# MICROCONTROLLER.net
KiCad netlist of a schematic drawn in Altium Designer
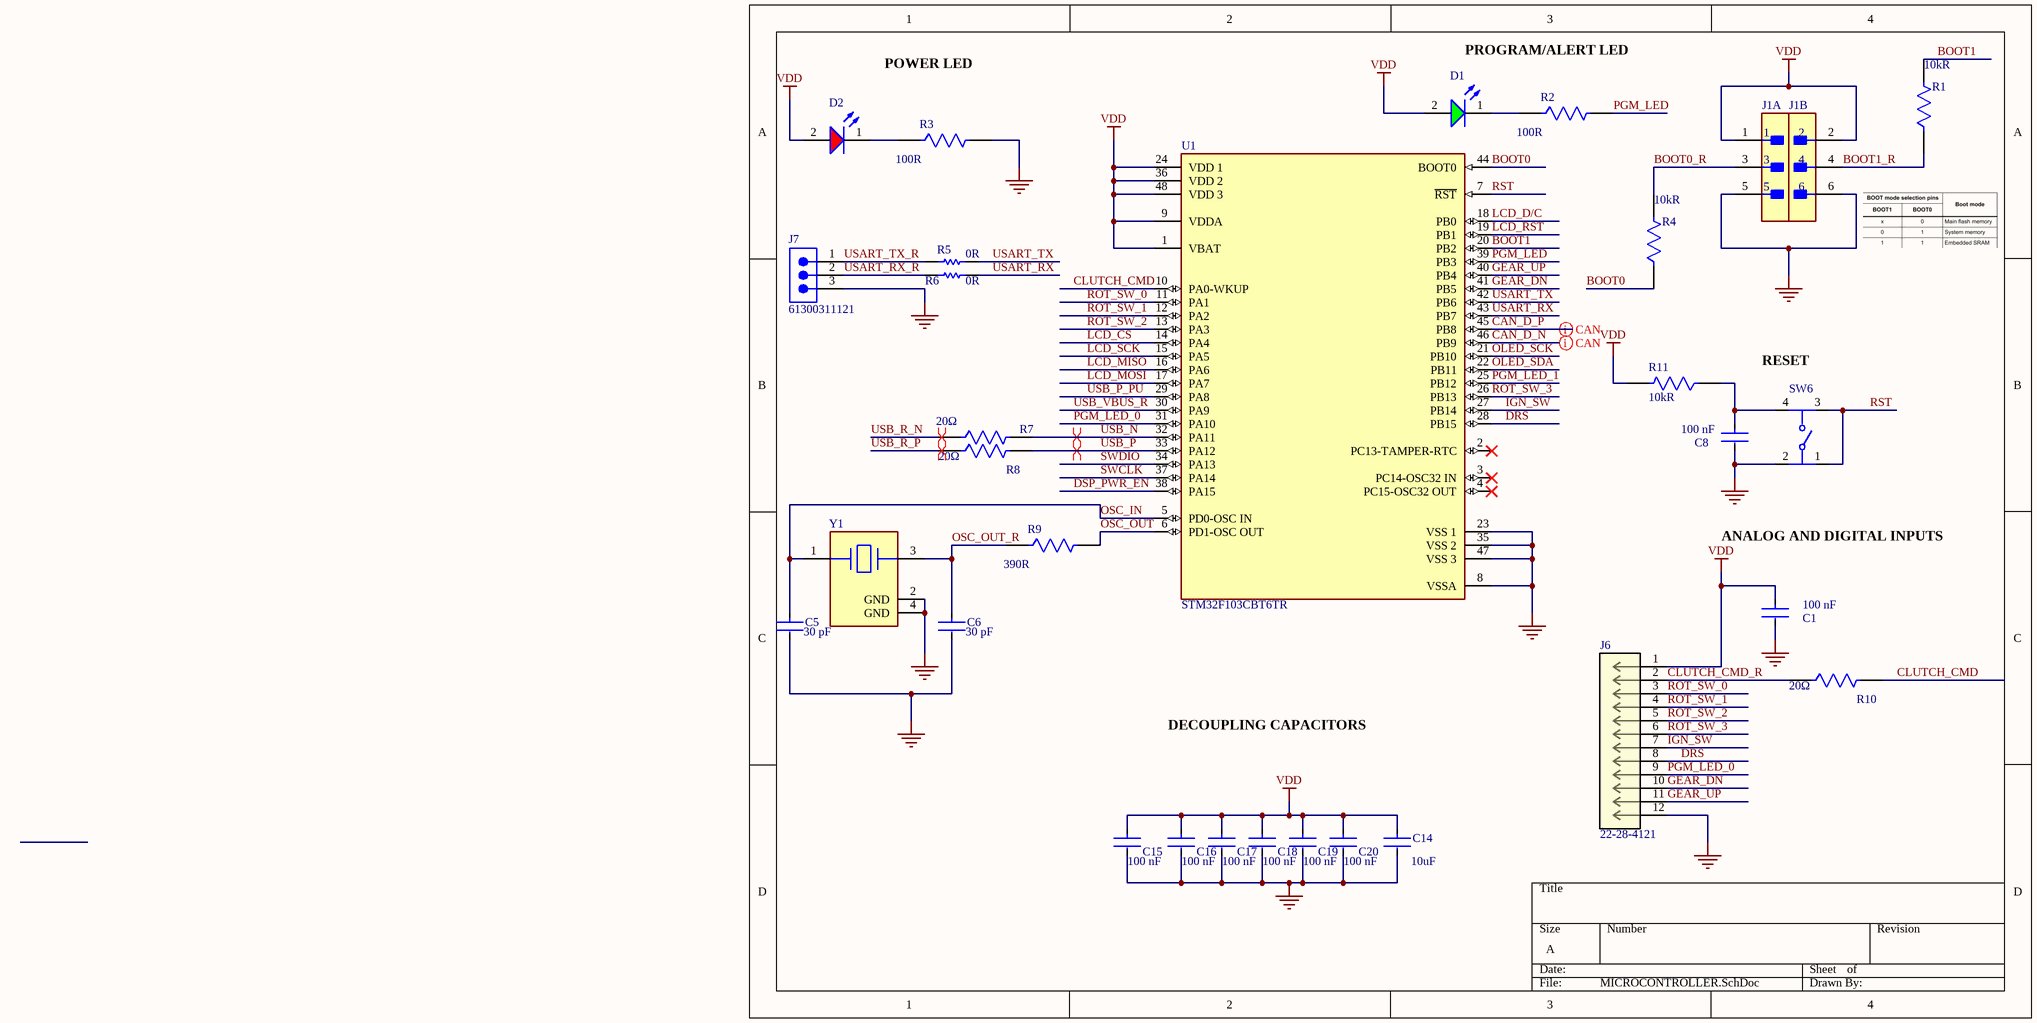
[diagram p0: MICROCONTROLLER.SchDoc]

(export (version "E")
  (design (tool "Eeschema 10.0.6"))
  (components
    (comp (ref "C1")
      (value "CC0402KRX7R7BB104")
      (footprint "FP-CC0402-MFG")
      (description "CAP CER 0.1UF 16V X7R 0402")
      (fields
        (field (name "CAPACITANCE") "100 nF")
        (field (name "MANUFACTURER") "YAGEO")
        (field (name "TOLERANCE") "0.1")
      )
      (libsource (lib "Altium Content Vault") (part "11868f565c42a9108669ba33697ecf6"))
    )
    (comp (ref "C5")
      (value "C0603C300F3HACAUTO")
      (footprint "FP-C0603C-CF-MFG")
      (description "C0603 30 pF X8R 30ppm/°C 1.00% 25 V")
      (fields
        (field (name "MANUFACTURER") "KEMET")
        (field (name "CAPACITANCE") "30 pF")
        (field (name "OCTOPART") "https://octopart.com/c0603c300f3hacauto-kemet-88087312")
      )
      (libsource (lib "Altium Content Vault") (part "b4654b650e69147ec39a6b967a45e02"))
    )
    (comp (ref "C6")
      (value "C0603C300F3HACAUTO")
      (footprint "FP-C0603C-CF-MFG")
      (description "C0603 30 pF X8R 30ppm/°C 1.00% 25 V")
      (fields
        (field (name "MANUFACTURER") "KEMET")
        (field (name "CAPACITANCE") "30 pF")
        (field (name "OCTOPART") "https://octopart.com/c0603c300f3hacauto-kemet-88087312")
      )
      (libsource (lib "Altium Content Vault") (part "b4654b650e69147ec39a6b967a45e02"))
    )
    (comp (ref "C8")
      (value "CC0402KRX7R7BB104")
      (footprint "FP-CC0402-MFG")
      (description "CAP CER 0.1UF 16V X7R 0402")
      (fields
        (field (name "CAPACITANCE") "100 nF")
        (field (name "MANUFACTURER") "YAGEO")
        (field (name "TOLERANCE") "0.1")
      )
      (libsource (lib "Altium Content Vault") (part "11868f565c42a9108669ba33697ecf6"))
    )
    (comp (ref "C14")
      (value "EMK212BB7106KG-T")
      (footprint "FP-0805-L_2_0_0_2-W_1_25-MFG")
      (description "CAP CER 10UF 16V X7R 0805")
      (fields (field (name "TOLERANCE") "10%") (field (name "CAPACITANCE") "10uF"))
      (libsource (lib "Altium Content Vault") (part "b4654b650e69147ec39a6b967a45e02"))
    )
    (comp (ref "C15")
      (value "CC0402KRX7R7BB104")
      (footprint "FP-CC0402-MFG")
      (description "CAP CER 0.1UF 16V X7R 0402")
      (fields
        (field (name "CAPACITANCE") "100 nF")
        (field (name "MANUFACTURER") "YAGEO")
        (field (name "TOLERANCE") "0.1")
      )
      (libsource (lib "Altium Content Vault") (part "11868f565c42a9108669ba33697ecf6"))
    )
    (comp (ref "C16")
      (value "CC0402KRX7R7BB104")
      (footprint "FP-CC0402-MFG")
      (description "CAP CER 0.1UF 16V X7R 0402")
      (fields
        (field (name "CAPACITANCE") "100 nF")
        (field (name "MANUFACTURER") "YAGEO")
        (field (name "TOLERANCE") "0.1")
      )
      (libsource (lib "Altium Content Vault") (part "11868f565c42a9108669ba33697ecf6"))
    )
    (comp (ref "C17")
      (value "CC0402KRX7R7BB104")
      (footprint "FP-CC0402-MFG")
      (description "CAP CER 0.1UF 16V X7R 0402")
      (fields
        (field (name "CAPACITANCE") "100 nF")
        (field (name "MANUFACTURER") "YAGEO")
        (field (name "TOLERANCE") "0.1")
      )
      (libsource (lib "Altium Content Vault") (part "11868f565c42a9108669ba33697ecf6"))
    )
    (comp (ref "C18")
      (value "CC0402KRX7R7BB104")
      (footprint "FP-CC0402-MFG")
      (description "CAP CER 0.1UF 16V X7R 0402")
      (fields
        (field (name "CAPACITANCE") "100 nF")
        (field (name "MANUFACTURER") "YAGEO")
        (field (name "TOLERANCE") "0.1")
      )
      (libsource (lib "Altium Content Vault") (part "11868f565c42a9108669ba33697ecf6"))
    )
    (comp (ref "C19")
      (value "CC0402KRX7R7BB104")
      (footprint "FP-CC0402-MFG")
      (description "CAP CER 0.1UF 16V X7R 0402")
      (fields
        (field (name "CAPACITANCE") "100 nF")
        (field (name "MANUFACTURER") "YAGEO")
        (field (name "TOLERANCE") "0.1")
      )
      (libsource (lib "Altium Content Vault") (part "11868f565c42a9108669ba33697ecf6"))
    )
    (comp (ref "C20")
      (value "CC0402KRX7R7BB104")
      (footprint "FP-CC0402-MFG")
      (description "CAP CER 0.1UF 16V X7R 0402")
      (fields
        (field (name "CAPACITANCE") "100 nF")
        (field (name "MANUFACTURER") "YAGEO")
        (field (name "TOLERANCE") "0.1")
      )
      (libsource (lib "Altium Content Vault") (part "11868f565c42a9108669ba33697ecf6"))
    )
    (comp (ref "D1")
      (value "150060VS75000")
      (footprint "WL-SMCW_0603_150060xx75000")
      (description "WURTH ELEKTRONIK - 150060VS75000 - LED, Green, SMD, 0603, 30 mA, 2 V, 570 nm")
      (libsource (lib "Altium Content Vault") (part "LED_Green_2A-1K"))
    )
    (comp (ref "D2")
      (value "150080RS75000")
      (footprint "WL-SMCW_0805_150080xx75000")
      (description "LED Uni-Color Red 630nm 2-Pin Chip 0805(2012Metric) T/R")
      (libsource (lib "Altium Content Vault") (part "LED_Red_2A-1K"))
    )
    (comp (ref "J1")
      (value "FTSH-103-01-F-DV-TR")
      (footprint "FP-FTSH-103-01-F-DV-TR-MFG")
      (description "CONN HEADER SMD 6POS 1.27MM")
      (libsource (lib "") (part "2654a11fb13586ecb194516b1c997bc_1"))
    )
    (comp (ref "J6")
      (value "22-28-4121")
      (footprint "12 POS_2.54MM_MOLEX")
      (description "KK 254 Breakaway Header, Vertical, 12 Circuits, Tin (Sn) Plating, Mating Pin Length 8.13mm")
      (fields (field (name "MANUFACTURER") "Molex"))
      (libsource (lib "F1_MODULE") (part "22-28-4121"))
    )
    (comp (ref "J7")
      (value "61300311121")
      (footprint "61300311121")
      (description "CONN HEADER VERT 3POS 2.54MM")
      (libsource (lib "Altium Content Vault") (part "Header_Male_1R_03P"))
    )
    (comp (ref "R1")
      (value "RC0402JR-0710KL")
      (footprint "FP-RC0402-0_4-MFG")
      (description "RES 10K OHM 5% 1/16W 0402")
      (fields (field (name "RESISTANCE") "10kR") (field (name "TOLERANCE") "5%"))
      (libsource (lib "Altium Content Vault") (part "1029c3af85768c4190bb7ad29bc67b5"))
    )
    (comp (ref "R2")
      (value "MCS0402MC1000FE000")
      (footprint "FP-MCS0402-MFG")
      (description "RES SMD 1.2K OHM 1% 1/10W 0402")
      (fields (field (name "RESISTANCE") "100R") (field (name "TOLERANCE") "1%"))
      (libsource (lib "Altium Content Vault") (part "1029c3af85768c4190bb7ad29bc67b5"))
    )
    (comp (ref "R3")
      (value "MCS0402MC1000FE000")
      (footprint "FP-MCS0402-MFG")
      (description "RES SMD 1.2K OHM 1% 1/10W 0402")
      (fields (field (name "RESISTANCE") "100R") (field (name "TOLERANCE") "1%"))
      (libsource (lib "Altium Content Vault") (part "1029c3af85768c4190bb7ad29bc67b5"))
    )
    (comp (ref "R4")
      (value "RC0402JR-0710KL")
      (footprint "FP-RC0402-0_4-MFG")
      (description "RES 10K OHM 5% 1/16W 0402")
      (fields (field (name "RESISTANCE") "10kR") (field (name "TOLERANCE") "5%"))
      (libsource (lib "Altium Content Vault") (part "1029c3af85768c4190bb7ad29bc67b5"))
    )
    (comp (ref "R5")
      (value "ERJ2GE0R00X")
      (footprint "RESC1005X40X25LL05T05")
      (description "Chip Resistor, 0 Ohm, 0.1 W, -55 to 155 degC, 0402 (1005 Metric), RoHS, Tape and Reel")
      (fields
        (field (name "MANUFACTURER") "Panasonic")
        (field (name "RESISTANCE") "0R")
        (field (name "TOLERANCE") "5%")
      )
      (libsource (lib "Altium Content Vault") (part "RES-2"))
    )
    (comp (ref "R6")
      (value "ERJ2GE0R00X")
      (footprint "RESC1005X40X25LL05T05")
      (description "Chip Resistor, 0 Ohm, 0.1 W, -55 to 155 degC, 0402 (1005 Metric), RoHS, Tape and Reel")
      (fields
        (field (name "MANUFACTURER") "Panasonic")
        (field (name "RESISTANCE") "0R")
        (field (name "TOLERANCE") "5%")
      )
      (libsource (lib "Altium Content Vault") (part "RES-2"))
    )
    (comp (ref "R7")
      (value "RT0402FRE0720RL")
      (footprint "FP-RT0402-MFG")
      (description "RES SMD 20 OHM 1% 1/16W 0402")
      (fields
        (field (name "RESISTANCE") "20Ω")
        (field (name "MANUFACTURER") "Yageo")
        (field (name "OCTOPART") "https://octopart.com/rt0402fre0720rl-yageo-1278881")
      )
      (libsource (lib "Altium Content Vault") (part "1029c3af85768c4190bb7ad29bc67b5"))
    )
    (comp (ref "R8")
      (value "RT0402FRE0720RL")
      (footprint "FP-RT0402-MFG")
      (description "RES SMD 20 OHM 1% 1/16W 0402")
      (fields
        (field (name "RESISTANCE") "20Ω")
        (field (name "MANUFACTURER") "Yageo")
        (field (name "OCTOPART") "https://octopart.com/rt0402fre0720rl-yageo-1278881")
      )
      (libsource (lib "Altium Content Vault") (part "1029c3af85768c4190bb7ad29bc67b5"))
    )
    (comp (ref "R9")
      (value "CRCW0402390RFKED")
      (footprint "FP-CRCW0402-e3-MFG")
      (description "RES Thick Film, 390Ω, 1%, 0.063W, 100ppm/°C, 0402")
      (fields (field (name "RESISTANCE") "390R") (field (name "TOLERANCE") "1%"))
      (libsource (lib "Altium Content Vault") (part "1029c3af85768c4190bb7ad29bc67b5"))
    )
    (comp (ref "R10")
      (value "RT0402FRE0720RL")
      (footprint "FP-RT0402-MFG")
      (description "RES SMD 20 OHM 1% 1/16W 0402")
      (fields
        (field (name "RESISTANCE") "20Ω")
        (field (name "MANUFACTURER") "Yageo")
        (field (name "OCTOPART") "https://octopart.com/rt0402fre0720rl-yageo-1278881")
      )
      (libsource (lib "Altium Content Vault") (part "1029c3af85768c4190bb7ad29bc67b5"))
    )
    (comp (ref "R11")
      (value "RC0402JR-0710KL")
      (footprint "FP-RC0402-0_4-MFG")
      (description "RES 10K OHM 5% 1/16W 0402")
      (fields (field (name "RESISTANCE") "10kR") (field (name "TOLERANCE") "5%"))
      (libsource (lib "Altium Content Vault") (part "1029c3af85768c4190bb7ad29bc67b5"))
    )
    (comp (ref "SW6")
      (value "1977223-4")
      (footprint "FP-1977223-4-MFG")
      (description "SWITCH TACTILE SPST-NO 0.05A 12V")
      (libsource (lib "Altium Content Vault") (part "b8895f3f4cefb76e1819d2863dba89b"))
    )
    (comp (ref "U1")
      (value "STM32F103CBT6TR")
      (footprint "FP-LQFP48-5B-MFG")
      (description "ARM® Cortex®-M3 STM32F1 Microcontroller IC 32-Bit 72MHz 128KB (128K x 8) FLASH")
      (libsource (lib "Altium Content Vault") (part "2bc3fe5586cf3d28b17275e4580a88a"))
    )
    (comp (ref "Y1")
      (value "ABM3BAIG-8.000MHZ-1Z-T")
      (footprint "FP-ABM3BAIG-MFG")
      (description "CRYSTAL 8.0000MHZ 18PF SMD")
      (libsource (lib "Altium Content Vault") (part "3dd7ae69e6a56028198fd7abc02d048"))
    )
  )
  (nets
    (net (code "1") (name "/BOOT0") (class "Default")
      (node (ref "R4") (pin "1") (pinfunction "1_1") (pintype "passive"))
      (node (ref "U1") (pin "44") (pinfunction "BOOT0_44") (pintype "input"))
    )
    (net (code "2") (name "/BOOT0_R") (class "Default")
      (node (ref "J1") (pin "3") (pinfunction "3_3") (pintype "passive"))
      (node (ref "R4") (pin "2") (pinfunction "2_2") (pintype "passive"))
    )
    (net (code "3") (name "/BOOT1") (class "Default")
      (node (ref "R1") (pin "2") (pinfunction "2_2") (pintype "passive"))
      (node (ref "U1") (pin "20") (pinfunction "PB2_20") (pintype "bidirectional"))
    )
    (net (code "4") (name "/BOOT1_R") (class "Default")
      (node (ref "J1") (pin "4") (pinfunction "4_4") (pintype "passive"))
      (node (ref "R1") (pin "1") (pinfunction "1_1") (pintype "passive"))
    )
    (net (code "5") (name "/CAN_D_N") (class "Default")
      (node (ref "U1") (pin "46") (pinfunction "PB9_46") (pintype "bidirectional"))
    )
    (net (code "6") (name "/CAN_D_P") (class "Default")
      (node (ref "U1") (pin "45") (pinfunction "PB8_45") (pintype "bidirectional"))
    )
    (net (code "7") (name "/CLUTCH_CMD") (class "Default")
      (node (ref "R10") (pin "2") (pinfunction "2_2") (pintype "passive"))
      (node (ref "U1") (pin "10") (pinfunction "PA0-WKUP_10") (pintype "bidirectional"))
    )
    (net (code "8") (name "/CLUTCH_CMD_R") (class "Default")
      (node (ref "J6") (pin "2") (pinfunction "2_2") (pintype "passive"))
      (node (ref "R10") (pin "1") (pinfunction "1_1") (pintype "passive"))
    )
    (net (code "9") (name "/DRS") (class "Default")
      (node (ref "J6") (pin "8") (pinfunction "8_8") (pintype "passive"))
      (node (ref "U1") (pin "28") (pinfunction "PB15_28") (pintype "bidirectional"))
    )
    (net (code "10") (name "/DSP_PWR_EN") (class "Default")
      (node (ref "U1") (pin "38") (pinfunction "PA15_38") (pintype "bidirectional"))
    )
    (net (code "11") (name "/GEAR_DN") (class "Default")
      (node (ref "J6") (pin "10") (pinfunction "10_10") (pintype "passive"))
      (node (ref "U1") (pin "41") (pinfunction "PB5_41") (pintype "bidirectional"))
    )
    (net (code "12") (name "/GEAR_UP") (class "Default")
      (node (ref "J6") (pin "11") (pinfunction "11_11") (pintype "passive"))
      (node (ref "U1") (pin "40") (pinfunction "PB4_40") (pintype "bidirectional"))
    )
    (net (code "13") (name "/IGN_SW") (class "Default")
      (node (ref "J6") (pin "7") (pinfunction "7_7") (pintype "passive"))
      (node (ref "U1") (pin "27") (pinfunction "PB14_27") (pintype "bidirectional"))
    )
    (net (code "14") (name "/LCD_CS") (class "Default")
      (node (ref "U1") (pin "14") (pinfunction "PA4_14") (pintype "bidirectional"))
    )
    (net (code "15") (name "/LCD_D{slash}C") (class "Default")
      (node (ref "U1") (pin "18") (pinfunction "PB0_18") (pintype "bidirectional"))
    )
    (net (code "16") (name "/LCD_MISO") (class "Default")
      (node (ref "U1") (pin "16") (pinfunction "PA6_16") (pintype "bidirectional"))
    )
    (net (code "17") (name "/LCD_MOSI") (class "Default")
      (node (ref "U1") (pin "17") (pinfunction "PA7_17") (pintype "bidirectional"))
    )
    (net (code "18") (name "/LCD_RST") (class "Default")
      (node (ref "U1") (pin "19") (pinfunction "PB1_19") (pintype "bidirectional"))
    )
    (net (code "19") (name "/LCD_SCK") (class "Default")
      (node (ref "U1") (pin "15") (pinfunction "PA5_15") (pintype "bidirectional"))
    )
    (net (code "20") (name "/OLED_SCK") (class "Default")
      (node (ref "U1") (pin "21") (pinfunction "PB10_21") (pintype "bidirectional"))
    )
    (net (code "21") (name "/OLED_SDA") (class "Default")
      (node (ref "U1") (pin "22") (pinfunction "PB11_22") (pintype "bidirectional"))
    )
    (net (code "22") (name "/OSC_IN") (class "Default")
      (node (ref "C5") (pin "1") (pinfunction "1_1") (pintype "passive"))
      (node (ref "U1") (pin "5") (pinfunction "PD0-OSC_IN_5") (pintype "bidirectional"))
      (node (ref "Y1") (pin "1") (pinfunction "1_1") (pintype "passive"))
    )
    (net (code "23") (name "/OSC_OUT") (class "Default")
      (node (ref "R9") (pin "2") (pinfunction "2_2") (pintype "passive"))
      (node (ref "U1") (pin "6") (pinfunction "PD1-OSC_OUT_6") (pintype "bidirectional"))
    )
    (net (code "24") (name "/OSC_OUT_R") (class "Default")
      (node (ref "C6") (pin "1") (pinfunction "1_1") (pintype "passive"))
      (node (ref "R9") (pin "1") (pinfunction "1_1") (pintype "passive"))
      (node (ref "Y1") (pin "3") (pinfunction "3_3") (pintype "passive"))
    )
    (net (code "25") (name "/PGM_LED") (class "Default")
      (node (ref "R2") (pin "2") (pinfunction "2_2") (pintype "passive"))
      (node (ref "U1") (pin "39") (pinfunction "PB3_39") (pintype "bidirectional"))
    )
    (net (code "26") (name "/PGM_LED_0") (class "Default")
      (node (ref "J6") (pin "9") (pinfunction "9_9") (pintype "passive"))
      (node (ref "U1") (pin "31") (pinfunction "PA10_31") (pintype "bidirectional"))
    )
    (net (code "27") (name "/PGM_LED_1") (class "Default")
      (node (ref "U1") (pin "25") (pinfunction "PB12_25") (pintype "bidirectional"))
    )
    (net (code "28") (name "/ROT_SW_0") (class "Default")
      (node (ref "J6") (pin "3") (pinfunction "3_3") (pintype "passive"))
      (node (ref "U1") (pin "11") (pinfunction "PA1_11") (pintype "bidirectional"))
    )
    (net (code "29") (name "/ROT_SW_1") (class "Default")
      (node (ref "J6") (pin "4") (pinfunction "4_4") (pintype "passive"))
      (node (ref "U1") (pin "12") (pinfunction "PA2_12") (pintype "bidirectional"))
    )
    (net (code "30") (name "/ROT_SW_2") (class "Default")
      (node (ref "J6") (pin "5") (pinfunction "5_5") (pintype "passive"))
      (node (ref "U1") (pin "13") (pinfunction "PA3_13") (pintype "bidirectional"))
    )
    (net (code "31") (name "/ROT_SW_3") (class "Default")
      (node (ref "J6") (pin "6") (pinfunction "6_6") (pintype "passive"))
      (node (ref "U1") (pin "26") (pinfunction "PB13_26") (pintype "bidirectional"))
    )
    (net (code "32") (name "/RST") (class "Default")
      (node (ref "SW6") (pin "1") (pinfunction "1_1") (pintype "passive"))
      (node (ref "SW6") (pin "3") (pinfunction "3_3") (pintype "passive"))
      (node (ref "U1") (pin "7") (pinfunction "~{RST}_7") (pintype "input"))
    )
    (net (code "33") (name "/SWCLK") (class "Default")
      (node (ref "U1") (pin "37") (pinfunction "PA14_37") (pintype "bidirectional"))
    )
    (net (code "34") (name "/SWDIO") (class "Default")
      (node (ref "U1") (pin "34") (pinfunction "PA13_34") (pintype "bidirectional"))
    )
    (net (code "35") (name "/USART_RX") (class "Default")
      (node (ref "R6") (pin "2") (pinfunction "2_2") (pintype "passive"))
      (node (ref "U1") (pin "43") (pinfunction "PB7_43") (pintype "bidirectional"))
    )
    (net (code "36") (name "/USART_RX_R") (class "Default")
      (node (ref "J7") (pin "2") (pinfunction "2_2") (pintype "passive"))
      (node (ref "R6") (pin "1") (pinfunction "1_1") (pintype "passive"))
    )
    (net (code "37") (name "/USART_TX") (class "Default")
      (node (ref "R5") (pin "2") (pinfunction "2_2") (pintype "passive"))
      (node (ref "U1") (pin "42") (pinfunction "PB6_42") (pintype "bidirectional"))
    )
    (net (code "38") (name "/USART_TX_R") (class "Default")
      (node (ref "J7") (pin "1") (pinfunction "1_1") (pintype "passive"))
      (node (ref "R5") (pin "1") (pinfunction "1_1") (pintype "passive"))
    )
    (net (code "39") (name "/USB_N") (class "Default")
      (node (ref "R7") (pin "2") (pinfunction "2_2") (pintype "passive"))
      (node (ref "U1") (pin "32") (pinfunction "PA11_32") (pintype "bidirectional"))
    )
    (net (code "40") (name "/USB_P") (class "Default")
      (node (ref "R8") (pin "2") (pinfunction "2_2") (pintype "passive"))
      (node (ref "U1") (pin "33") (pinfunction "PA12_33") (pintype "bidirectional"))
    )
    (net (code "41") (name "/USB_P_PU") (class "Default")
      (node (ref "U1") (pin "29") (pinfunction "PA8_29") (pintype "bidirectional"))
    )
    (net (code "42") (name "/USB_R_N") (class "Default")
      (node (ref "R7") (pin "1") (pinfunction "1_1") (pintype "passive"))
    )
    (net (code "43") (name "/USB_R_P") (class "Default")
      (node (ref "R8") (pin "1") (pinfunction "1_1") (pintype "passive"))
    )
    (net (code "44") (name "/USB_VBUS_R") (class "Default")
      (node (ref "U1") (pin "30") (pinfunction "PA9_30") (pintype "bidirectional"))
    )
    (net (code "45") (name "GND") (class "Default")
      (node (ref "C1") (pin "2") (pinfunction "2_2") (pintype "passive"))
      (node (ref "C14") (pin "2") (pinfunction "2_2") (pintype "passive"))
      (node (ref "C15") (pin "2") (pinfunction "2_2") (pintype "passive"))
      (node (ref "C16") (pin "2") (pinfunction "2_2") (pintype "passive"))
      (node (ref "C17") (pin "2") (pinfunction "2_2") (pintype "passive"))
      (node (ref "C18") (pin "2") (pinfunction "2_2") (pintype "passive"))
      (node (ref "C19") (pin "2") (pinfunction "2_2") (pintype "passive"))
      (node (ref "C20") (pin "2") (pinfunction "2_2") (pintype "passive"))
      (node (ref "C5") (pin "2") (pinfunction "2_2") (pintype "passive"))
      (node (ref "C6") (pin "2") (pinfunction "2_2") (pintype "passive"))
      (node (ref "C8") (pin "2") (pinfunction "2_2") (pintype "passive"))
      (node (ref "J1") (pin "5") (pinfunction "5_5") (pintype "passive"))
      (node (ref "J1") (pin "6") (pinfunction "6_6") (pintype "passive"))
      (node (ref "J6") (pin "12") (pinfunction "12_12") (pintype "passive"))
      (node (ref "J7") (pin "3") (pinfunction "3_3") (pintype "passive"))
      (node (ref "R3") (pin "2") (pinfunction "2_2") (pintype "passive"))
      (node (ref "SW6") (pin "2") (pinfunction "2_2") (pintype "passive"))
      (node (ref "U1") (pin "23") (pinfunction "VSS_1_23") (pintype "power_in"))
      (node (ref "U1") (pin "35") (pinfunction "VSS_2_35") (pintype "power_in"))
      (node (ref "U1") (pin "47") (pinfunction "VSS_3_47") (pintype "power_in"))
      (node (ref "U1") (pin "8") (pinfunction "VSSA_8") (pintype "power_in"))
      (node (ref "Y1") (pin "2") (pinfunction "GND_2") (pintype "power_in"))
      (node (ref "Y1") (pin "4") (pinfunction "GND_4") (pintype "power_in"))
    )
    (net (code "46") (name "Net-(C8-Pad1)") (class "Default")
      (node (ref "C8") (pin "1") (pinfunction "1_1") (pintype "passive"))
      (node (ref "R11") (pin "1") (pinfunction "1_1") (pintype "passive"))
      (node (ref "SW6") (pin "4") (pinfunction "4_4") (pintype "passive"))
    )
    (net (code "47") (name "Net-(D1-K)") (class "Default")
      (node (ref "D1") (pin "1") (pinfunction "K_1") (pintype "passive"))
      (node (ref "R2") (pin "1") (pinfunction "1_1") (pintype "passive"))
    )
    (net (code "48") (name "Net-(D2-K)") (class "Default")
      (node (ref "D2") (pin "1") (pinfunction "K_1") (pintype "passive"))
      (node (ref "R3") (pin "1") (pinfunction "1_1") (pintype "passive"))
    )
    (net (code "49") (name "VDD") (class "Default")
      (node (ref "C1") (pin "1") (pinfunction "1_1") (pintype "passive"))
      (node (ref "C14") (pin "1") (pinfunction "1_1") (pintype "passive"))
      (node (ref "C15") (pin "1") (pinfunction "1_1") (pintype "passive"))
      (node (ref "C16") (pin "1") (pinfunction "1_1") (pintype "passive"))
      (node (ref "C17") (pin "1") (pinfunction "1_1") (pintype "passive"))
      (node (ref "C18") (pin "1") (pinfunction "1_1") (pintype "passive"))
      (node (ref "C19") (pin "1") (pinfunction "1_1") (pintype "passive"))
      (node (ref "C20") (pin "1") (pinfunction "1_1") (pintype "passive"))
      (node (ref "D1") (pin "2") (pinfunction "A_2") (pintype "passive"))
      (node (ref "D2") (pin "2") (pinfunction "A_2") (pintype "passive"))
      (node (ref "J1") (pin "1") (pinfunction "1_1") (pintype "passive"))
      (node (ref "J1") (pin "2") (pinfunction "2_2") (pintype "passive"))
      (node (ref "J6") (pin "1") (pinfunction "1_1") (pintype "passive"))
      (node (ref "R11") (pin "2") (pinfunction "2_2") (pintype "passive"))
      (node (ref "U1") (pin "1") (pinfunction "VBAT_1") (pintype "power_in"))
      (node (ref "U1") (pin "24") (pinfunction "VDD_1_24") (pintype "power_in"))
      (node (ref "U1") (pin "36") (pinfunction "VDD_2_36") (pintype "power_in"))
      (node (ref "U1") (pin "48") (pinfunction "VDD_3_48") (pintype "power_in"))
      (node (ref "U1") (pin "9") (pinfunction "VDDA_9") (pintype "power_in"))
    )
    (net (code "50") (name "unconnected-(U1-PC13-TAMPER-RTC-Pad2)") (class "Default")
      (node (ref "U1") (pin "2") (pinfunction "PC13-TAMPER-RTC_2") (pintype "bidirectional+no_connect"))
    )
    (net (code "51") (name "unconnected-(U1-PC14-OSC32_IN-Pad3)") (class "Default")
      (node (ref "U1") (pin "3") (pinfunction "PC14-OSC32_IN_3") (pintype "bidirectional+no_connect"))
    )
    (net (code "52") (name "unconnected-(U1-PC15-OSC32_OUT-Pad4)") (class "Default")
      (node (ref "U1") (pin "4") (pinfunction "PC15-OSC32_OUT_4") (pintype "bidirectional+no_connect"))
    )
  )
)
